# T101.net
KiCad netlist of a schematic drawn in EAGLE
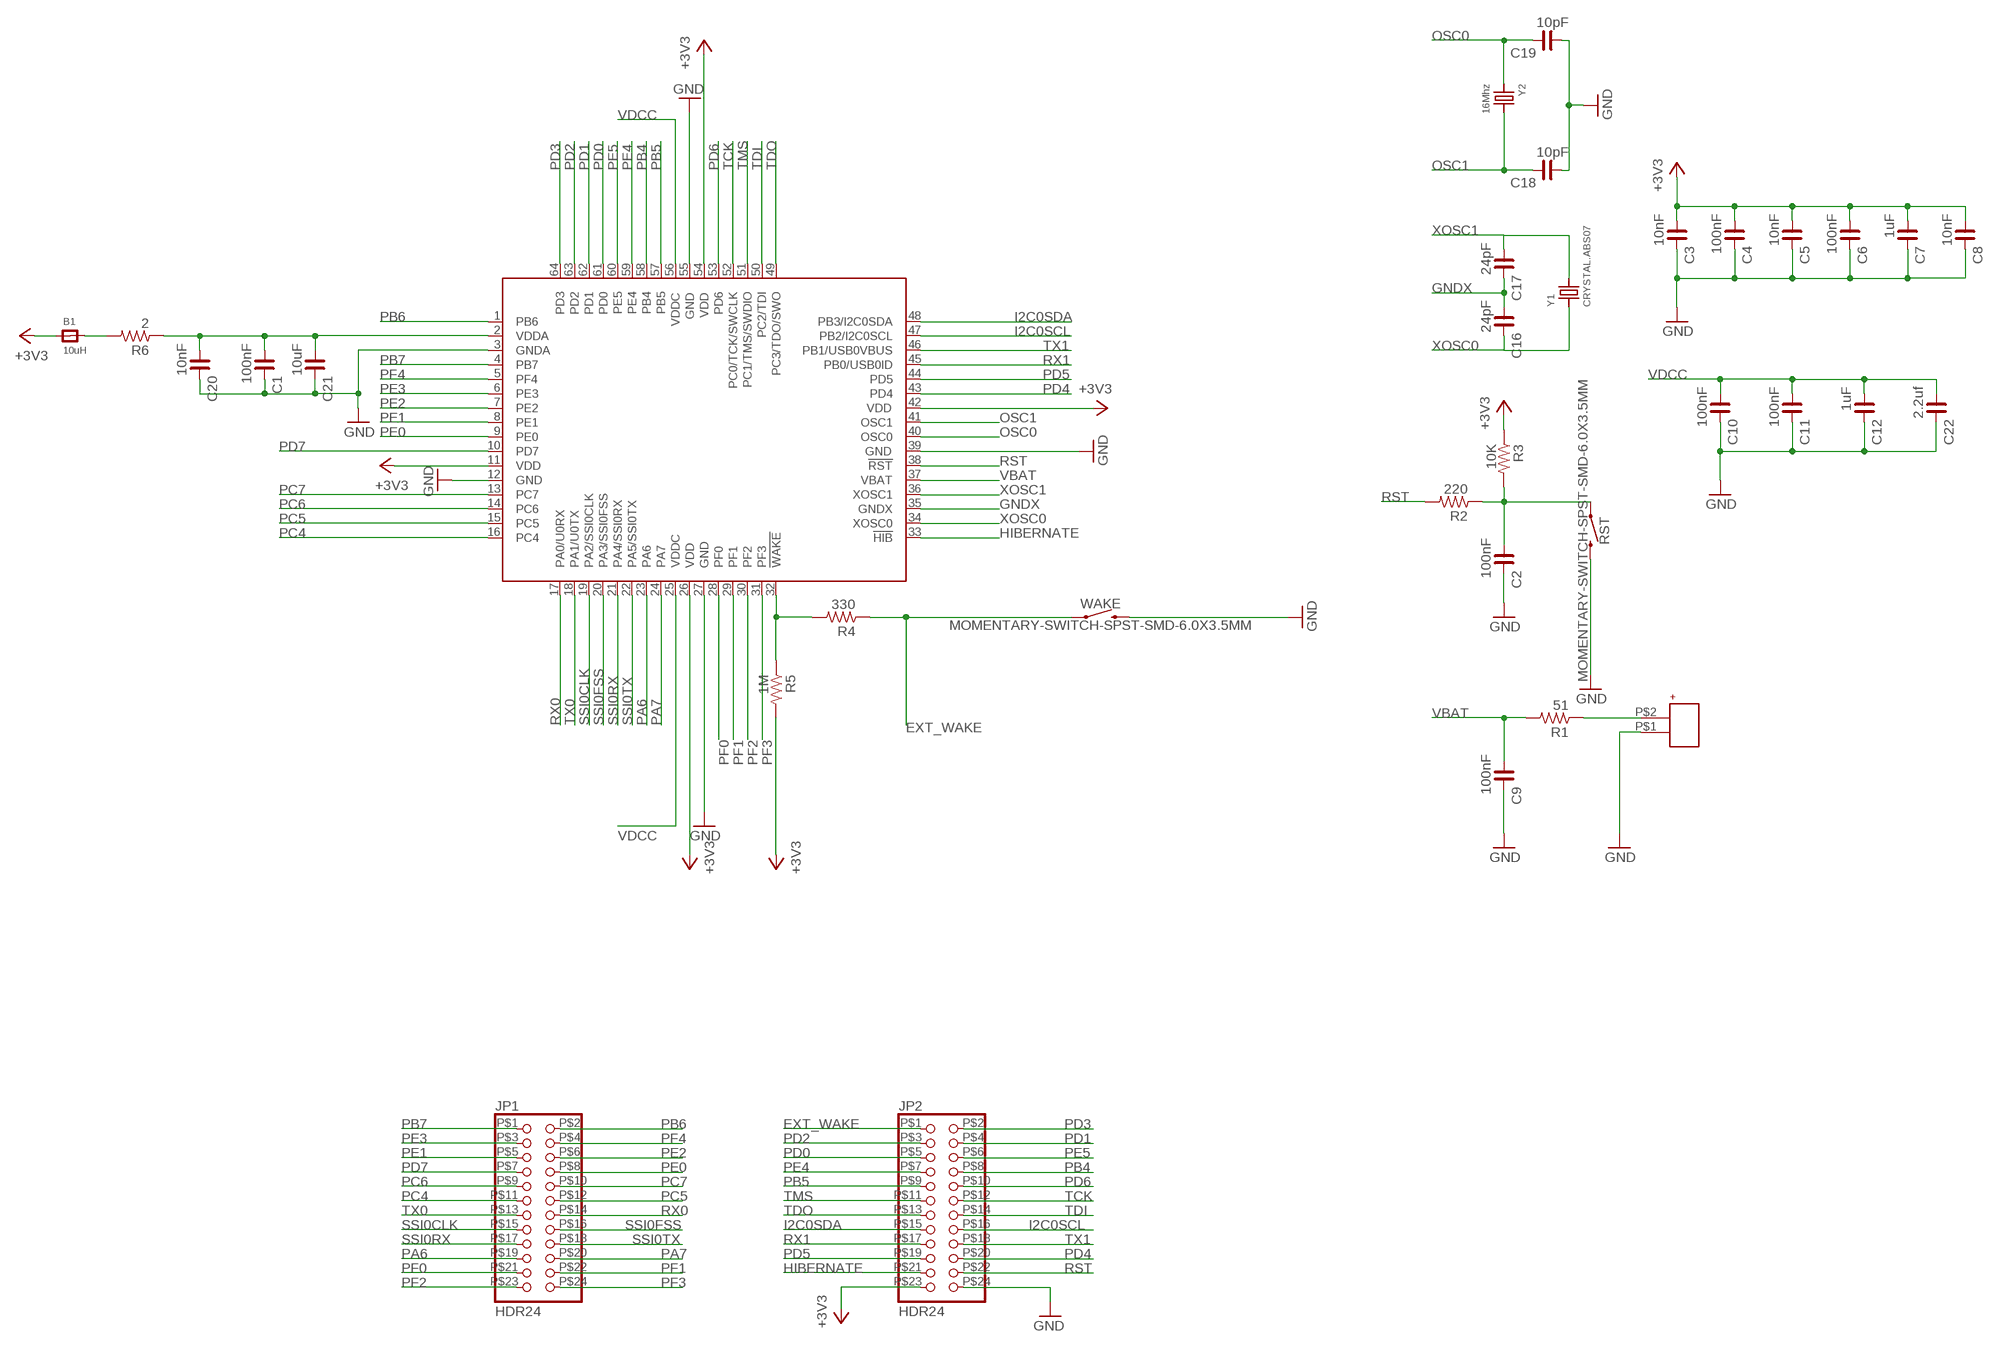
[diagram p0: schematic, sheet 1]

(export (version "E")
  (design (tool "Eeschema 10.0.6"))
  (components
    (comp (ref "B1")
      (value "10uH")
      (footprint "eagle-import:_0603")
      (libsource (lib "eagle-import") (part "FERRITE_0603"))
    )
    (comp (ref "C1")
      (value "100nF")
      (footprint "eagle-import:C0402")
      (libsource (lib "eagle-import") (part "C_0402"))
    )
    (comp (ref "C2")
      (value "100nF")
      (footprint "eagle-import:C0402")
      (libsource (lib "eagle-import") (part "C_0402"))
    )
    (comp (ref "C3")
      (value "10nF")
      (footprint "eagle-import:C0402")
      (libsource (lib "eagle-import") (part "C_0402"))
    )
    (comp (ref "C4")
      (value "100nF")
      (footprint "eagle-import:C0402")
      (libsource (lib "eagle-import") (part "C_0402"))
    )
    (comp (ref "C5")
      (value "10nF")
      (footprint "eagle-import:C0402")
      (libsource (lib "eagle-import") (part "C_0402"))
    )
    (comp (ref "C6")
      (value "100nF")
      (footprint "eagle-import:C0402")
      (libsource (lib "eagle-import") (part "C_0402"))
    )
    (comp (ref "C7")
      (value "1uF")
      (footprint "eagle-import:C0402")
      (libsource (lib "eagle-import") (part "C_0402"))
    )
    (comp (ref "C8")
      (value "10nF")
      (footprint "eagle-import:C0402")
      (libsource (lib "eagle-import") (part "C_0402"))
    )
    (comp (ref "C9")
      (value "100nF")
      (footprint "eagle-import:C0402")
      (libsource (lib "eagle-import") (part "C_0402"))
    )
    (comp (ref "C10")
      (value "100nF")
      (footprint "eagle-import:C0402")
      (libsource (lib "eagle-import") (part "C_0402"))
    )
    (comp (ref "C11")
      (value "100nF")
      (footprint "eagle-import:C0402")
      (libsource (lib "eagle-import") (part "C_0402"))
    )
    (comp (ref "C12")
      (value "1uF")
      (footprint "eagle-import:C0402")
      (libsource (lib "eagle-import") (part "C_0402"))
    )
    (comp (ref "C16")
      (value "24pF")
      (footprint "eagle-import:C0402")
      (libsource (lib "eagle-import") (part "C_0402"))
    )
    (comp (ref "C17")
      (value "24pF")
      (footprint "eagle-import:C0402")
      (libsource (lib "eagle-import") (part "C_0402"))
    )
    (comp (ref "C18")
      (value "10pF")
      (footprint "eagle-import:C0402")
      (libsource (lib "eagle-import") (part "C_0402"))
    )
    (comp (ref "C19")
      (value "10pF")
      (footprint "eagle-import:C0402")
      (libsource (lib "eagle-import") (part "C_0402"))
    )
    (comp (ref "C20")
      (value "10nF")
      (footprint "eagle-import:C0402")
      (libsource (lib "eagle-import") (part "C_0402"))
    )
    (comp (ref "C21")
      (value "10uF")
      (footprint "eagle-import:C0603")
      (libsource (lib "eagle-import") (part "C_0603"))
    )
    (comp (ref "C22")
      (value "2.2uf")
      (footprint "eagle-import:C0603")
      (libsource (lib "eagle-import") (part "C_0603"))
    )
    (comp (ref "IC1")
      (value "TM4C123[7,G]XXPM")
      (footprint "eagle-import:PM_S-PQFP-G64")
      (libsource (lib "eagle-import") (part "TM4C123[7,G]XXPM"))
    )
    (comp (ref "JP1")
      (value "HDR24")
      (footprint "eagle-import:HDR24")
      (libsource (lib "eagle-import") (part "HDR24"))
    )
    (comp (ref "JP2")
      (value "HDR24")
      (footprint "eagle-import:HDR24")
      (libsource (lib "eagle-import") (part "HDR24"))
    )
    (comp (ref "R1")
      (value "51")
      (footprint "eagle-import:R0402")
      (libsource (lib "eagle-import") (part "R_0402"))
    )
    (comp (ref "R2")
      (value "220")
      (footprint "eagle-import:R0402")
      (libsource (lib "eagle-import") (part "R_0402"))
    )
    (comp (ref "R3")
      (value "10K")
      (footprint "eagle-import:R0402")
      (libsource (lib "eagle-import") (part "R_0402"))
    )
    (comp (ref "R4")
      (value "330")
      (footprint "eagle-import:R0402")
      (libsource (lib "eagle-import") (part "R_0402"))
    )
    (comp (ref "R5")
      (value "1M")
      (footprint "eagle-import:R0402")
      (libsource (lib "eagle-import") (part "R_0402"))
    )
    (comp (ref "R6")
      (value "2")
      (footprint "eagle-import:R0402")
      (libsource (lib "eagle-import") (part "R_0402"))
    )
    (comp (ref "RST")
      (value "MOMENTARY-SWITCH-SPST-SMD-6.0X3.5MM")
      (footprint "eagle-import:TACTILE_SWITCH_SMD_6.0X3.5MM")
      (libsource (lib "eagle-import") (part "MOMENTARY-SWITCH-SPST-SMD-6.0X3.5MM"))
    )
    (comp (ref "U$1")
      (value "JST-MICROBAT")
      (footprint "eagle-import:JST-MICROBAT")
      (libsource (lib "eagle-import") (part "JST-MICROBAT"))
    )
    (comp (ref "WAKE")
      (value "MOMENTARY-SWITCH-SPST-SMD-6.0X3.5MM")
      (footprint "eagle-import:TACTILE_SWITCH_SMD_6.0X3.5MM")
      (libsource (lib "eagle-import") (part "MOMENTARY-SWITCH-SPST-SMD-6.0X3.5MM"))
    )
    (comp (ref "Y1")
      (value "CRYSTAL.ABS07")
      (footprint "eagle-import:ABS07")
      (libsource (lib "eagle-import") (part "CRYSTAL.ABS07"))
    )
    (comp (ref "Y2")
      (value "16Mhz")
      (footprint "eagle-import:6X3.3MM")
      (libsource (lib "eagle-import") (part "CRYSTAL.6X3.3MM"))
    )
  )
  (nets
    (net (code "1") (name "+3V3") (class "Default")
      (node (ref "B1") (pin "1") (pinfunction "P$1_1") (pintype "passive"))
      (node (ref "C3") (pin "1") (pinfunction "1_1") (pintype "passive"))
      (node (ref "C4") (pin "1") (pinfunction "1_1") (pintype "passive"))
      (node (ref "C5") (pin "1") (pinfunction "1_1") (pintype "passive"))
      (node (ref "C6") (pin "1") (pinfunction "1_1") (pintype "passive"))
      (node (ref "C7") (pin "1") (pinfunction "1_1") (pintype "passive"))
      (node (ref "C8") (pin "1") (pinfunction "1_1") (pintype "passive"))
      (node (ref "IC1") (pin "11") (pinfunction "VDD_11") (pintype "bidirectional"))
      (node (ref "IC1") (pin "26") (pinfunction "VDD_26") (pintype "bidirectional"))
      (node (ref "IC1") (pin "42") (pinfunction "VDD_42") (pintype "bidirectional"))
      (node (ref "IC1") (pin "54") (pinfunction "VDD_54") (pintype "bidirectional"))
      (node (ref "JP2") (pin "P$23") (pinfunction "23_P$23") (pintype "passive"))
      (node (ref "R3") (pin "1") (pinfunction "1_1") (pintype "passive"))
      (node (ref "R5") (pin "2") (pinfunction "2_2") (pintype "passive"))
    )
    (net (code "2") (name "/EXT_WAKE") (class "Default")
      (node (ref "JP2") (pin "P$1") (pinfunction "1_P$1") (pintype "passive"))
      (node (ref "R4") (pin "1") (pinfunction "1_1") (pintype "passive"))
      (node (ref "WAKE") (pin "1") (pinfunction "1_1") (pintype "passive"))
    )
    (net (code "3") (name "/GNDX") (class "Default")
      (node (ref "C16") (pin "1") (pinfunction "1_1") (pintype "passive"))
      (node (ref "C17") (pin "2") (pinfunction "2_2") (pintype "passive"))
      (node (ref "IC1") (pin "35") (pinfunction "GNDX_35") (pintype "bidirectional"))
    )
    (net (code "4") (name "/HIBERNATE") (class "Default")
      (node (ref "IC1") (pin "33") (pinfunction "~{HIB}_33") (pintype "bidirectional"))
      (node (ref "JP2") (pin "P$21") (pinfunction "21_P$21") (pintype "passive"))
    )
    (net (code "5") (name "/I2C0SCL") (class "Default")
      (node (ref "IC1") (pin "47") (pinfunction "PB2/I2C0SCL_47") (pintype "bidirectional"))
      (node (ref "JP2") (pin "P$16") (pinfunction "16_P$16") (pintype "passive"))
    )
    (net (code "6") (name "/I2C0SDA") (class "Default")
      (node (ref "IC1") (pin "48") (pinfunction "PB3/I2C0SDA_48") (pintype "bidirectional"))
      (node (ref "JP2") (pin "P$15") (pinfunction "15_P$15") (pintype "passive"))
    )
    (net (code "7") (name "/OSC0") (class "Default")
      (node (ref "C19") (pin "2") (pinfunction "2_2") (pintype "passive"))
      (node (ref "IC1") (pin "40") (pinfunction "OSC0_40") (pintype "bidirectional"))
      (node (ref "Y2") (pin "1") (pinfunction "1_1") (pintype "passive"))
    )
    (net (code "8") (name "/OSC1") (class "Default")
      (node (ref "C18") (pin "2") (pinfunction "2_2") (pintype "passive"))
      (node (ref "IC1") (pin "41") (pinfunction "OSC1_41") (pintype "bidirectional"))
      (node (ref "Y2") (pin "2") (pinfunction "2_2") (pintype "passive"))
    )
    (net (code "9") (name "/PA6") (class "Default")
      (node (ref "IC1") (pin "23") (pinfunction "PA6_23") (pintype "bidirectional"))
      (node (ref "JP1") (pin "P$19") (pinfunction "19_P$19") (pintype "passive"))
    )
    (net (code "10") (name "/PA7") (class "Default")
      (node (ref "IC1") (pin "24") (pinfunction "PA7_24") (pintype "bidirectional"))
      (node (ref "JP1") (pin "P$20") (pinfunction "20_P$20") (pintype "passive"))
    )
    (net (code "11") (name "/PB4") (class "Default")
      (node (ref "IC1") (pin "58") (pinfunction "PB4_58") (pintype "bidirectional"))
      (node (ref "JP2") (pin "P$8") (pinfunction "8_P$8") (pintype "passive"))
    )
    (net (code "12") (name "/PB5") (class "Default")
      (node (ref "IC1") (pin "57") (pinfunction "PB5_57") (pintype "bidirectional"))
      (node (ref "JP2") (pin "P$9") (pinfunction "9_P$9") (pintype "passive"))
    )
    (net (code "13") (name "/PB6") (class "Default")
      (node (ref "IC1") (pin "1") (pinfunction "PB6_1") (pintype "bidirectional"))
      (node (ref "JP1") (pin "P$2") (pinfunction "2_P$2") (pintype "passive"))
    )
    (net (code "14") (name "/PB7") (class "Default")
      (node (ref "IC1") (pin "4") (pinfunction "PB7_4") (pintype "bidirectional"))
      (node (ref "JP1") (pin "P$1") (pinfunction "1_P$1") (pintype "passive"))
    )
    (net (code "15") (name "/PC4") (class "Default")
      (node (ref "IC1") (pin "16") (pinfunction "PC4_16") (pintype "bidirectional"))
      (node (ref "JP1") (pin "P$11") (pinfunction "11_P$11") (pintype "passive"))
    )
    (net (code "16") (name "/PC5") (class "Default")
      (node (ref "IC1") (pin "15") (pinfunction "PC5_15") (pintype "bidirectional"))
      (node (ref "JP1") (pin "P$12") (pinfunction "12_P$12") (pintype "passive"))
    )
    (net (code "17") (name "/PC6") (class "Default")
      (node (ref "IC1") (pin "14") (pinfunction "PC6_14") (pintype "bidirectional"))
      (node (ref "JP1") (pin "P$9") (pinfunction "9_P$9") (pintype "passive"))
    )
    (net (code "18") (name "/PC7") (class "Default")
      (node (ref "IC1") (pin "13") (pinfunction "PC7_13") (pintype "bidirectional"))
      (node (ref "JP1") (pin "P$10") (pinfunction "10_P$10") (pintype "passive"))
    )
    (net (code "19") (name "/PD0") (class "Default")
      (node (ref "IC1") (pin "61") (pinfunction "PD0_61") (pintype "bidirectional"))
      (node (ref "JP2") (pin "P$5") (pinfunction "5_P$5") (pintype "passive"))
    )
    (net (code "20") (name "/PD1") (class "Default")
      (node (ref "IC1") (pin "62") (pinfunction "PD1_62") (pintype "bidirectional"))
      (node (ref "JP2") (pin "P$4") (pinfunction "4_P$4") (pintype "passive"))
    )
    (net (code "21") (name "/PD2") (class "Default")
      (node (ref "IC1") (pin "63") (pinfunction "PD2_63") (pintype "bidirectional"))
      (node (ref "JP2") (pin "P$3") (pinfunction "3_P$3") (pintype "passive"))
    )
    (net (code "22") (name "/PD3") (class "Default")
      (node (ref "IC1") (pin "64") (pinfunction "PD3_64") (pintype "bidirectional"))
      (node (ref "JP2") (pin "P$2") (pinfunction "2_P$2") (pintype "passive"))
    )
    (net (code "23") (name "/PD4") (class "Default")
      (node (ref "IC1") (pin "43") (pinfunction "PD4_43") (pintype "bidirectional"))
      (node (ref "JP2") (pin "P$20") (pinfunction "20_P$20") (pintype "passive"))
    )
    (net (code "24") (name "/PD5") (class "Default")
      (node (ref "IC1") (pin "44") (pinfunction "PD5_44") (pintype "bidirectional"))
      (node (ref "JP2") (pin "P$19") (pinfunction "19_P$19") (pintype "passive"))
    )
    (net (code "25") (name "/PD6") (class "Default")
      (node (ref "IC1") (pin "53") (pinfunction "PD6_53") (pintype "bidirectional"))
      (node (ref "JP2") (pin "P$10") (pinfunction "10_P$10") (pintype "passive"))
    )
    (net (code "26") (name "/PD7") (class "Default")
      (node (ref "IC1") (pin "10") (pinfunction "PD7_10") (pintype "bidirectional"))
      (node (ref "JP1") (pin "P$7") (pinfunction "7_P$7") (pintype "passive"))
    )
    (net (code "27") (name "/PE0") (class "Default")
      (node (ref "IC1") (pin "9") (pinfunction "PE0_9") (pintype "bidirectional"))
      (node (ref "JP1") (pin "P$8") (pinfunction "8_P$8") (pintype "passive"))
    )
    (net (code "28") (name "/PE1") (class "Default")
      (node (ref "IC1") (pin "8") (pinfunction "PE1_8") (pintype "bidirectional"))
      (node (ref "JP1") (pin "P$5") (pinfunction "5_P$5") (pintype "passive"))
    )
    (net (code "29") (name "/PE2") (class "Default")
      (node (ref "IC1") (pin "7") (pinfunction "PE2_7") (pintype "bidirectional"))
      (node (ref "JP1") (pin "P$6") (pinfunction "6_P$6") (pintype "passive"))
    )
    (net (code "30") (name "/PE3") (class "Default")
      (node (ref "IC1") (pin "6") (pinfunction "PE3_6") (pintype "bidirectional"))
      (node (ref "JP1") (pin "P$3") (pinfunction "3_P$3") (pintype "passive"))
    )
    (net (code "31") (name "/PE4") (class "Default")
      (node (ref "IC1") (pin "59") (pinfunction "PE4_59") (pintype "bidirectional"))
      (node (ref "JP2") (pin "P$7") (pinfunction "7_P$7") (pintype "passive"))
    )
    (net (code "32") (name "/PE5") (class "Default")
      (node (ref "IC1") (pin "60") (pinfunction "PE5_60") (pintype "bidirectional"))
      (node (ref "JP2") (pin "P$6") (pinfunction "6_P$6") (pintype "passive"))
    )
    (net (code "33") (name "/PF0") (class "Default")
      (node (ref "IC1") (pin "28") (pinfunction "PF0_28") (pintype "bidirectional"))
      (node (ref "JP1") (pin "P$21") (pinfunction "21_P$21") (pintype "passive"))
    )
    (net (code "34") (name "/PF1") (class "Default")
      (node (ref "IC1") (pin "29") (pinfunction "PF1_29") (pintype "bidirectional"))
      (node (ref "JP1") (pin "P$22") (pinfunction "22_P$22") (pintype "passive"))
    )
    (net (code "35") (name "/PF2") (class "Default")
      (node (ref "IC1") (pin "30") (pinfunction "PF2_30") (pintype "bidirectional"))
      (node (ref "JP1") (pin "P$23") (pinfunction "23_P$23") (pintype "passive"))
    )
    (net (code "36") (name "/PF3") (class "Default")
      (node (ref "IC1") (pin "31") (pinfunction "PF3_31") (pintype "bidirectional"))
      (node (ref "JP1") (pin "P$24") (pinfunction "24_P$24") (pintype "passive"))
    )
    (net (code "37") (name "/PF4") (class "Default")
      (node (ref "IC1") (pin "5") (pinfunction "PF4_5") (pintype "bidirectional"))
      (node (ref "JP1") (pin "P$4") (pinfunction "4_P$4") (pintype "passive"))
    )
    (net (code "38") (name "/RST") (class "Default")
      (node (ref "IC1") (pin "38") (pinfunction "~{RST}_38") (pintype "bidirectional"))
      (node (ref "JP2") (pin "P$22") (pinfunction "22_P$22") (pintype "passive"))
      (node (ref "R2") (pin "2") (pinfunction "2_2") (pintype "passive"))
    )
    (net (code "39") (name "/RX0") (class "Default")
      (node (ref "IC1") (pin "17") (pinfunction "PA0/U0RX_17") (pintype "bidirectional"))
      (node (ref "JP1") (pin "P$14") (pinfunction "14_P$14") (pintype "passive"))
    )
    (net (code "40") (name "/RX1") (class "Default")
      (node (ref "IC1") (pin "45") (pinfunction "PB0/USB0ID_45") (pintype "bidirectional"))
      (node (ref "JP2") (pin "P$17") (pinfunction "17_P$17") (pintype "passive"))
    )
    (net (code "41") (name "/SSI0CLK") (class "Default")
      (node (ref "IC1") (pin "19") (pinfunction "PA2/SSI0CLK_19") (pintype "bidirectional"))
      (node (ref "JP1") (pin "P$15") (pinfunction "15_P$15") (pintype "passive"))
    )
    (net (code "42") (name "/SSI0FSS") (class "Default")
      (node (ref "IC1") (pin "20") (pinfunction "PA3/SSI0FSS_20") (pintype "bidirectional"))
      (node (ref "JP1") (pin "P$16") (pinfunction "16_P$16") (pintype "passive"))
    )
    (net (code "43") (name "/SSI0RX") (class "Default")
      (node (ref "IC1") (pin "21") (pinfunction "PA4/SSI0RX_21") (pintype "bidirectional"))
      (node (ref "JP1") (pin "P$17") (pinfunction "17_P$17") (pintype "passive"))
    )
    (net (code "44") (name "/SSI0TX") (class "Default")
      (node (ref "IC1") (pin "22") (pinfunction "PA5/SSI0TX_22") (pintype "bidirectional"))
      (node (ref "JP1") (pin "P$18") (pinfunction "18_P$18") (pintype "passive"))
    )
    (net (code "45") (name "/TCK") (class "Default")
      (node (ref "IC1") (pin "52") (pinfunction "PC0/TCK/SWCLK_52") (pintype "bidirectional"))
      (node (ref "JP2") (pin "P$12") (pinfunction "12_P$12") (pintype "passive"))
    )
    (net (code "46") (name "/TDI") (class "Default")
      (node (ref "IC1") (pin "50") (pinfunction "PC2/TDI_50") (pintype "bidirectional"))
      (node (ref "JP2") (pin "P$14") (pinfunction "14_P$14") (pintype "passive"))
    )
    (net (code "47") (name "/TDO") (class "Default")
      (node (ref "IC1") (pin "49") (pinfunction "PC3/TDO/SWO_49") (pintype "bidirectional"))
      (node (ref "JP2") (pin "P$13") (pinfunction "13_P$13") (pintype "passive"))
    )
    (net (code "48") (name "/TMS") (class "Default")
      (node (ref "IC1") (pin "51") (pinfunction "PC1/TMS/SWDIO_51") (pintype "bidirectional"))
      (node (ref "JP2") (pin "P$11") (pinfunction "11_P$11") (pintype "passive"))
    )
    (net (code "49") (name "/TX0") (class "Default")
      (node (ref "IC1") (pin "18") (pinfunction "PA1/U0TX_18") (pintype "bidirectional"))
      (node (ref "JP1") (pin "P$13") (pinfunction "13_P$13") (pintype "passive"))
    )
    (net (code "50") (name "/TX1") (class "Default")
      (node (ref "IC1") (pin "46") (pinfunction "PB1/USB0VBUS_46") (pintype "bidirectional"))
      (node (ref "JP2") (pin "P$18") (pinfunction "18_P$18") (pintype "passive"))
    )
    (net (code "51") (name "/VBAT") (class "Default")
      (node (ref "C9") (pin "1") (pinfunction "1_1") (pintype "passive"))
      (node (ref "IC1") (pin "37") (pinfunction "VBAT_37") (pintype "bidirectional"))
      (node (ref "R1") (pin "2") (pinfunction "2_2") (pintype "passive"))
    )
    (net (code "52") (name "/VDCC") (class "Default")
      (node (ref "C10") (pin "1") (pinfunction "1_1") (pintype "passive"))
      (node (ref "C11") (pin "1") (pinfunction "1_1") (pintype "passive"))
      (node (ref "C12") (pin "1") (pinfunction "1_1") (pintype "passive"))
      (node (ref "C22") (pin "1") (pinfunction "1_1") (pintype "passive"))
      (node (ref "IC1") (pin "25") (pinfunction "VDDC_25") (pintype "bidirectional"))
      (node (ref "IC1") (pin "56") (pinfunction "VDDC_56") (pintype "bidirectional"))
    )
    (net (code "53") (name "/XOSC0") (class "Default")
      (node (ref "C16") (pin "2") (pinfunction "2_2") (pintype "passive"))
      (node (ref "IC1") (pin "34") (pinfunction "XOSC0_34") (pintype "bidirectional"))
      (node (ref "Y1") (pin "1") (pinfunction "1_1") (pintype "passive"))
    )
    (net (code "54") (name "/XOSC1") (class "Default")
      (node (ref "C17") (pin "1") (pinfunction "1_1") (pintype "passive"))
      (node (ref "IC1") (pin "36") (pinfunction "XOSC1_36") (pintype "bidirectional"))
      (node (ref "Y1") (pin "2") (pinfunction "2_2") (pintype "passive"))
    )
    (net (code "55") (name "GND") (class "Default")
      (node (ref "C1") (pin "2") (pinfunction "2_2") (pintype "passive"))
      (node (ref "C10") (pin "2") (pinfunction "2_2") (pintype "passive"))
      (node (ref "C11") (pin "2") (pinfunction "2_2") (pintype "passive"))
      (node (ref "C12") (pin "2") (pinfunction "2_2") (pintype "passive"))
      (node (ref "C18") (pin "1") (pinfunction "1_1") (pintype "passive"))
      (node (ref "C19") (pin "1") (pinfunction "1_1") (pintype "passive"))
      (node (ref "C2") (pin "2") (pinfunction "2_2") (pintype "passive"))
      (node (ref "C20") (pin "2") (pinfunction "2_2") (pintype "passive"))
      (node (ref "C21") (pin "2") (pinfunction "2_2") (pintype "passive"))
      (node (ref "C22") (pin "2") (pinfunction "2_2") (pintype "passive"))
      (node (ref "C3") (pin "2") (pinfunction "2_2") (pintype "passive"))
      (node (ref "C4") (pin "2") (pinfunction "2_2") (pintype "passive"))
      (node (ref "C5") (pin "2") (pinfunction "2_2") (pintype "passive"))
      (node (ref "C6") (pin "2") (pinfunction "2_2") (pintype "passive"))
      (node (ref "C7") (pin "2") (pinfunction "2_2") (pintype "passive"))
      (node (ref "C8") (pin "2") (pinfunction "2_2") (pintype "passive"))
      (node (ref "C9") (pin "2") (pinfunction "2_2") (pintype "passive"))
      (node (ref "IC1") (pin "12") (pinfunction "GND_12") (pintype "bidirectional"))
      (node (ref "IC1") (pin "27") (pinfunction "GND_27") (pintype "bidirectional"))
      (node (ref "IC1") (pin "3") (pinfunction "GNDA_3") (pintype "bidirectional"))
      (node (ref "IC1") (pin "39") (pinfunction "GND_39") (pintype "bidirectional"))
      (node (ref "IC1") (pin "55") (pinfunction "GND_55") (pintype "bidirectional"))
      (node (ref "JP2") (pin "P$24") (pinfunction "24_P$24") (pintype "passive"))
      (node (ref "RST") (pin "2") (pinfunction "2_2") (pintype "passive"))
      (node (ref "U$1") (pin "P$1") (pinfunction "P$1_P$1") (pintype "bidirectional"))
      (node (ref "WAKE") (pin "2") (pinfunction "2_2") (pintype "passive"))
    )
    (net (code "56") (name "Net-(B1-P$2)") (class "Default")
      (node (ref "B1") (pin "2") (pinfunction "P$2_2") (pintype "passive"))
      (node (ref "R6") (pin "2") (pinfunction "2_2") (pintype "passive"))
    )
    (net (code "57") (name "Net-(C2-Pad1)") (class "Default")
      (node (ref "C2") (pin "1") (pinfunction "1_1") (pintype "passive"))
      (node (ref "R2") (pin "1") (pinfunction "1_1") (pintype "passive"))
      (node (ref "R3") (pin "2") (pinfunction "2_2") (pintype "passive"))
      (node (ref "RST") (pin "1") (pinfunction "1_1") (pintype "passive"))
    )
    (net (code "58") (name "Net-(IC1-VDDA)") (class "Default")
      (node (ref "C1") (pin "1") (pinfunction "1_1") (pintype "passive"))
      (node (ref "C20") (pin "1") (pinfunction "1_1") (pintype "passive"))
      (node (ref "C21") (pin "1") (pinfunction "1_1") (pintype "passive"))
      (node (ref "IC1") (pin "2") (pinfunction "VDDA_2") (pintype "bidirectional"))
      (node (ref "R6") (pin "1") (pinfunction "1_1") (pintype "passive"))
    )
    (net (code "59") (name "Net-(IC1-~{WAKE})") (class "Default")
      (node (ref "IC1") (pin "32") (pinfunction "~{WAKE}_32") (pintype "bidirectional"))
      (node (ref "R4") (pin "2") (pinfunction "2_2") (pintype "passive"))
      (node (ref "R5") (pin "1") (pinfunction "1_1") (pintype "passive"))
    )
    (net (code "60") (name "Net-(R1-Pad1)") (class "Default")
      (node (ref "R1") (pin "1") (pinfunction "1_1") (pintype "passive"))
      (node (ref "U$1") (pin "P$2") (pinfunction "P$2_P$2") (pintype "bidirectional"))
    )
  )
)
